# sensor-tiny2313a.net
KiCad netlist of a schematic drawn in EAGLE
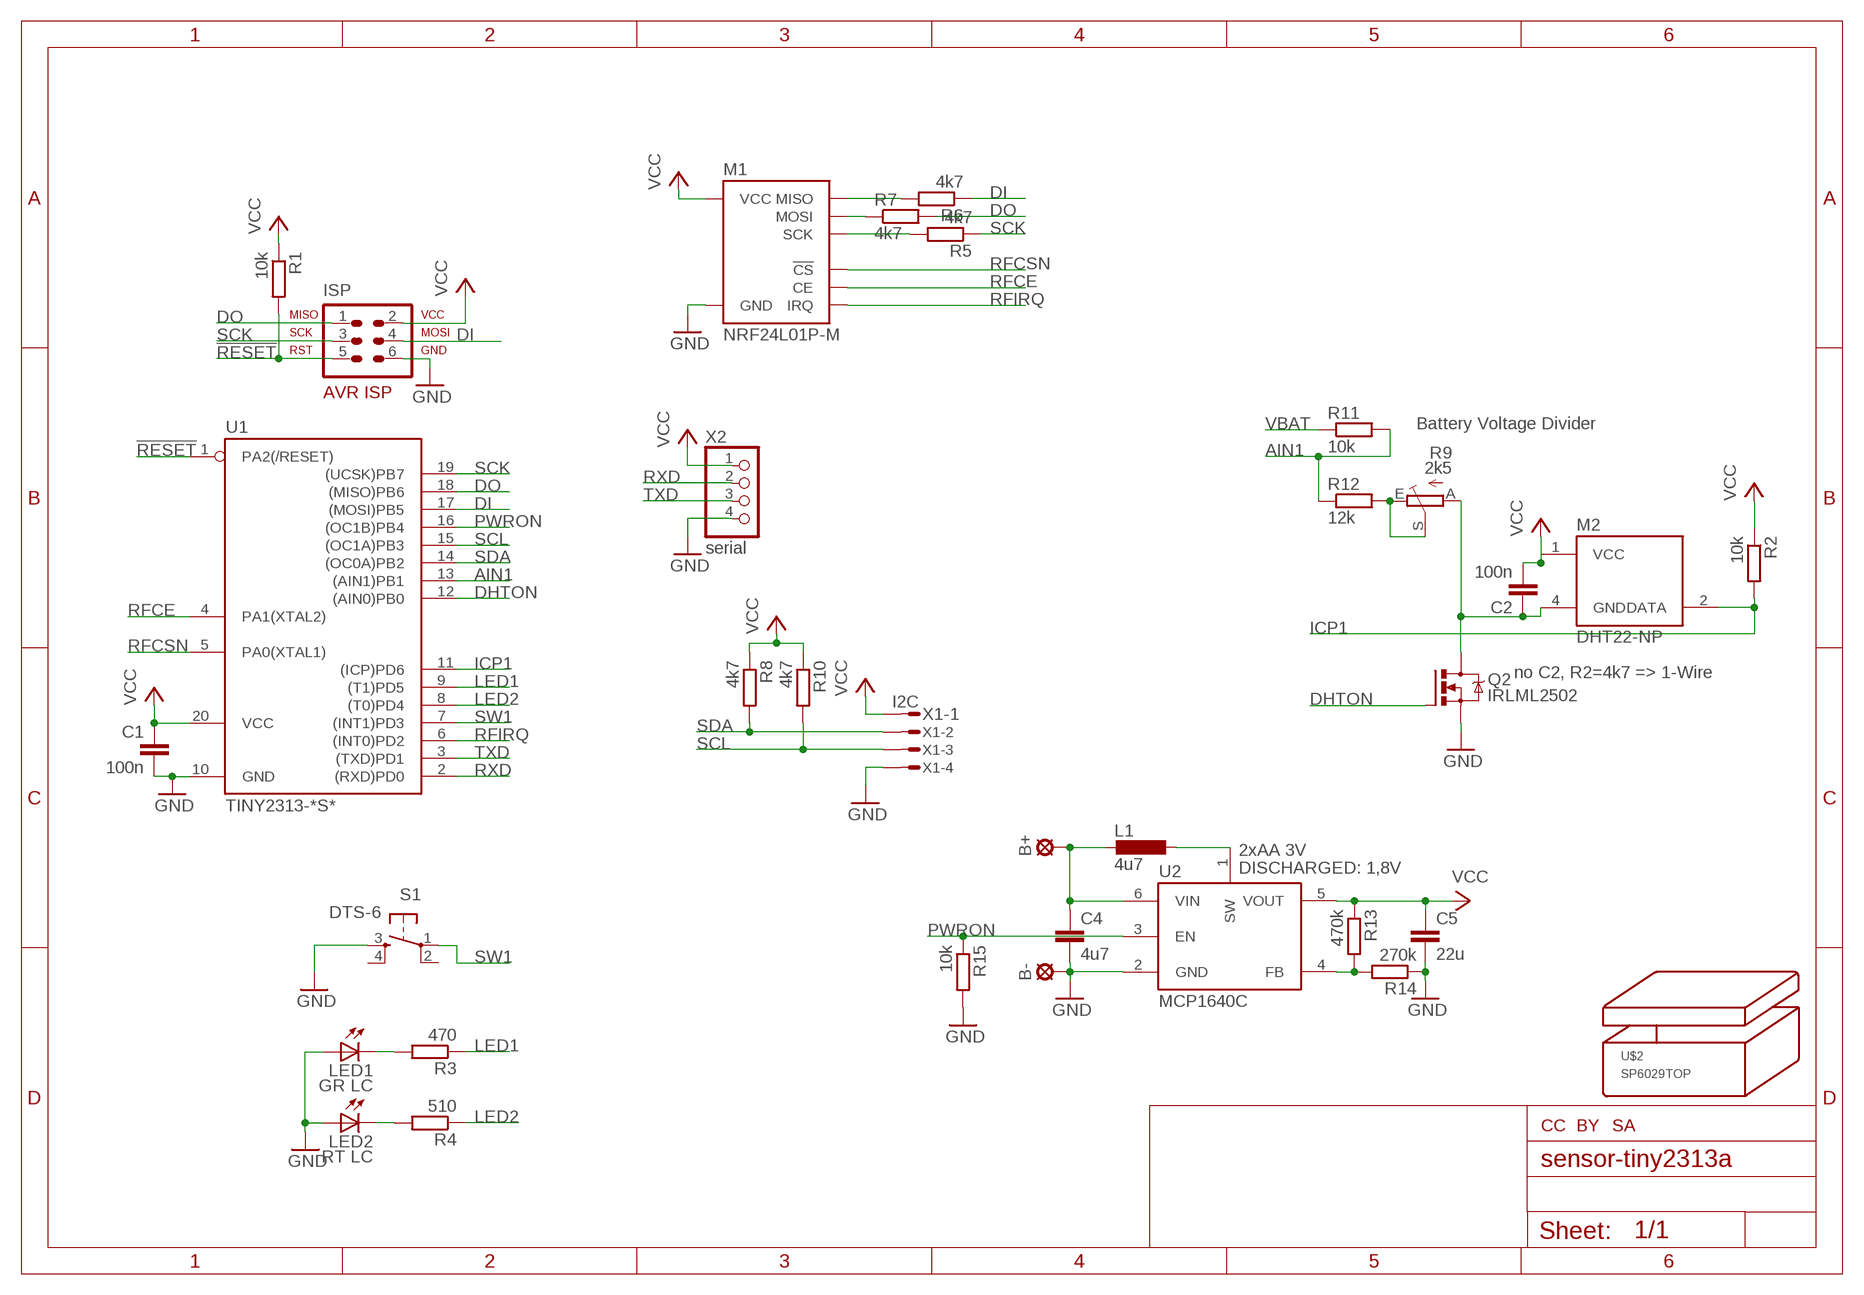
[diagram p0: schematic, sheet 1]

(export (version "E")
  (design (tool "Eeschema 10.0.6"))
  (components
    (comp (ref "B+")
      (value "LSP11")
      (footprint "eagle-import:LSP11")
      (libsource (lib "eagle-import") (part "LSP11"))
    )
    (comp (ref "B-")
      (value "LSP11")
      (footprint "eagle-import:LSP11")
      (libsource (lib "eagle-import") (part "LSP11"))
    )
    (comp (ref "C1")
      (value "100n")
      (footprint "eagle-import:C0603")
      (libsource (lib "eagle-import") (part "C-EUC0603"))
    )
    (comp (ref "C2")
      (value "100n")
      (footprint "eagle-import:C0603")
      (libsource (lib "eagle-import") (part "C-EUC0603"))
    )
    (comp (ref "C4")
      (value "4u7")
      (footprint "eagle-import:C0805")
      (libsource (lib "eagle-import") (part "C-EUC0805"))
    )
    (comp (ref "C5")
      (value "22u")
      (footprint "eagle-import:C1206")
      (libsource (lib "eagle-import") (part "C-EUC1206"))
    )
    (comp (ref "ISP")
      (value "ML6")
      (footprint "eagle-import:AVR-ISP-6")
      (libsource (lib "eagle-import") (part "AVR-ISP-6VERT"))
    )
    (comp (ref "L1")
      (value "4u7")
      (footprint "eagle-import:PISG")
      (libsource (lib "eagle-import") (part "L-EUPISG"))
    )
    (comp (ref "LED1")
      (value "GR LC")
      (footprint "eagle-import:LED5MM")
      (libsource (lib "eagle-import") (part "LED5MM"))
    )
    (comp (ref "LED2")
      (value "RT LC")
      (footprint "eagle-import:LED5MM")
      (libsource (lib "eagle-import") (part "LED5MM"))
    )
    (comp (ref "M1")
      (value "NRF24L01P-M")
      (footprint "eagle-import:NRF24L01P-A")
      (libsource (lib "eagle-import") (part "NRF24L01P-M"))
    )
    (comp (ref "M2")
      (value "DHT22-NP")
      (footprint "eagle-import:DHT22-NOPRINT")
      (libsource (lib "eagle-import") (part "DHT22-NP"))
    )
    (comp (ref "Q2")
      (value "IRLML2502")
      (footprint "eagle-import:MICRO3")
      (libsource (lib "eagle-import") (part "IRLML2502"))
    )
    (comp (ref "R1")
      (value "10k")
      (footprint "eagle-import:R0603")
      (libsource (lib "eagle-import") (part "R-EU_R0603"))
    )
    (comp (ref "R2")
      (value "10k")
      (footprint "eagle-import:R0603")
      (libsource (lib "eagle-import") (part "R-EU_R0603"))
    )
    (comp (ref "R3")
      (value "470")
      (footprint "eagle-import:R0603")
      (libsource (lib "eagle-import") (part "R-EU_R0603"))
    )
    (comp (ref "R4")
      (value "510")
      (footprint "eagle-import:R0603")
      (libsource (lib "eagle-import") (part "R-EU_R0603"))
    )
    (comp (ref "R5")
      (value "4k7")
      (footprint "eagle-import:R0603")
      (libsource (lib "eagle-import") (part "R-EU_R0603"))
    )
    (comp (ref "R6")
      (value "4k7")
      (footprint "eagle-import:R0603")
      (libsource (lib "eagle-import") (part "R-EU_R0603"))
    )
    (comp (ref "R7")
      (value "4k7")
      (footprint "eagle-import:R0603")
      (libsource (lib "eagle-import") (part "R-EU_R0603"))
    )
    (comp (ref "R8")
      (value "4k7")
      (footprint "eagle-import:R0603")
      (libsource (lib "eagle-import") (part "R-EU_R0603"))
    )
    (comp (ref "R9")
      (value "2k5")
      (footprint "eagle-import:CA6H")
      (libsource (lib "eagle-import") (part "TRIM_EU-CA6H"))
    )
    (comp (ref "R10")
      (value "4k7")
      (footprint "eagle-import:R0603")
      (libsource (lib "eagle-import") (part "R-EU_R0603"))
    )
    (comp (ref "R11")
      (value "10k")
      (footprint "eagle-import:R0603")
      (libsource (lib "eagle-import") (part "R-EU_R0603"))
    )
    (comp (ref "R12")
      (value "12k")
      (footprint "eagle-import:R0603")
      (libsource (lib "eagle-import") (part "R-EU_R0603"))
    )
    (comp (ref "R13")
      (value "470k")
      (footprint "eagle-import:R0603")
      (libsource (lib "eagle-import") (part "R-EU_R0603"))
    )
    (comp (ref "R14")
      (value "270k")
      (footprint "eagle-import:R0603")
      (libsource (lib "eagle-import") (part "R-EU_R0603"))
    )
    (comp (ref "R15")
      (value "10k")
      (footprint "eagle-import:R0603")
      (libsource (lib "eagle-import") (part "R-EU_R0603"))
    )
    (comp (ref "S1")
      (value "DTS-6")
      (footprint "eagle-import:DTS-6")
      (libsource (lib "eagle-import") (part "DTS-6"))
    )
    (comp (ref "U$1")
      (value "CC-TPLACE-HALF")
      (footprint "eagle-import:CC_TPLACE_HS")
      (libsource (lib "eagle-import") (part "CC-TPLACE-HALF"))
    )
    (comp (ref "U$2")
      (value "SP6029TOP")
      (footprint "eagle-import:SP6029T")
      (libsource (lib "eagle-import") (part "SP6029TOP"))
    )
    (comp (ref "U$3")
      (value "BY-TPLACE-HS")
      (footprint "eagle-import:BY_TPLACE_HS")
      (libsource (lib "eagle-import") (part "BY-TPLACE-HS"))
    )
    (comp (ref "U$4")
      (value "SA-TPLACE-HALF")
      (footprint "eagle-import:SA_TPLACE_HS")
      (libsource (lib "eagle-import") (part "SA-TPLACE-HALF"))
    )
    (comp (ref "U1")
      (value "TINY2313-*S*")
      (footprint "eagle-import:SO20L$")
      (libsource (lib "eagle-import") (part "TINY2313-S"))
    )
    (comp (ref "U2")
      (value "MCP1640C")
      (footprint "eagle-import:SOT23-6")
      (libsource (lib "eagle-import") (part "MCP1640"))
    )
    (comp (ref "X1")
      (value "I2C")
      (footprint "eagle-import:MICROMATCH-4")
      (libsource (lib "eagle-import") (part "MICROMATCH-4"))
    )
    (comp (ref "X2")
      (value "serial")
      (footprint "eagle-import:1X04")
      (libsource (lib "eagle-import") (part "PINHD-1X4_2.54"))
    )
  )
  (nets
    (net (code "1") (name "/AIN1") (class "Default")
      (node (ref "R11") (pin "2") (pinfunction "2_2") (pintype "passive"))
      (node (ref "R12") (pin "1") (pinfunction "1_1") (pintype "passive"))
      (node (ref "U1") (pin "13") (pinfunction "(AIN1)PB1_13") (pintype "bidirectional"))
    )
    (net (code "2") (name "/DHTON") (class "Default")
      (node (ref "Q2") (pin "1") (pinfunction "G_1") (pintype "passive"))
      (node (ref "U1") (pin "12") (pinfunction "(AIN0)PB0_12") (pintype "bidirectional"))
    )
    (net (code "3") (name "/DI") (class "Default")
      (node (ref "ISP") (pin "4") (pinfunction "4_4") (pintype "passive"))
      (node (ref "R6") (pin "1") (pinfunction "1_1") (pintype "passive"))
      (node (ref "U1") (pin "17") (pinfunction "(MOSI)PB5_17") (pintype "bidirectional"))
    )
    (net (code "4") (name "/DO") (class "Default")
      (node (ref "ISP") (pin "1") (pinfunction "1_1") (pintype "passive"))
      (node (ref "R7") (pin "2") (pinfunction "2_2") (pintype "passive"))
      (node (ref "U1") (pin "18") (pinfunction "(MISO)PB6_18") (pintype "bidirectional"))
    )
    (net (code "5") (name "/ICP1") (class "Default")
      (node (ref "M2") (pin "2") (pinfunction "DATA_2") (pintype "bidirectional"))
      (node (ref "R2") (pin "2") (pinfunction "2_2") (pintype "passive"))
      (node (ref "U1") (pin "11") (pinfunction "(ICP)PD6_11") (pintype "bidirectional"))
    )
    (net (code "6") (name "/LED1") (class "Default")
      (node (ref "R3") (pin "1") (pinfunction "1_1") (pintype "passive"))
      (node (ref "U1") (pin "9") (pinfunction "(T1)PD5_9") (pintype "bidirectional"))
    )
    (net (code "7") (name "/LED2") (class "Default")
      (node (ref "R4") (pin "1") (pinfunction "1_1") (pintype "passive"))
      (node (ref "U1") (pin "8") (pinfunction "(T0)PD4_8") (pintype "bidirectional"))
    )
    (net (code "8") (name "/PWRON") (class "Default")
      (node (ref "R15") (pin "1") (pinfunction "1_1") (pintype "passive"))
      (node (ref "U1") (pin "16") (pinfunction "(OC1B)PB4_16") (pintype "bidirectional"))
      (node (ref "U2") (pin "3") (pinfunction "EN_3") (pintype "input"))
    )
    (net (code "9") (name "/RFCE") (class "Default")
      (node (ref "M1") (pin "CE") (pinfunction "CE_CE") (pintype "input"))
      (node (ref "U1") (pin "4") (pinfunction "PA1(XTAL2)_4") (pintype "bidirectional"))
    )
    (net (code "10") (name "/RFCSN") (class "Default")
      (node (ref "M1") (pin "CSN") (pinfunction "~{CS}_CSN") (pintype "input"))
      (node (ref "U1") (pin "5") (pinfunction "PA0(XTAL1)_5") (pintype "bidirectional"))
    )
    (net (code "11") (name "/RFIRQ") (class "Default")
      (node (ref "M1") (pin "IRQ") (pinfunction "IRQ_IRQ") (pintype "output"))
      (node (ref "U1") (pin "6") (pinfunction "(INT0)PD2_6") (pintype "bidirectional"))
    )
    (net (code "12") (name "/RXD") (class "Default")
      (node (ref "U1") (pin "2") (pinfunction "(RXD)PD0_2") (pintype "bidirectional"))
      (node (ref "X2") (pin "2") (pinfunction "2_2") (pintype "passive"))
    )
    (net (code "13") (name "/SCK") (class "Default")
      (node (ref "ISP") (pin "3") (pinfunction "3_3") (pintype "passive"))
      (node (ref "R5") (pin "1") (pinfunction "1_1") (pintype "passive"))
      (node (ref "U1") (pin "19") (pinfunction "(UCSK)PB7_19") (pintype "bidirectional"))
    )
    (net (code "14") (name "/SCL") (class "Default")
      (node (ref "R10") (pin "2") (pinfunction "2_2") (pintype "passive"))
      (node (ref "U1") (pin "15") (pinfunction "(OC1A)PB3_15") (pintype "bidirectional"))
      (node (ref "X1") (pin "3") (pinfunction "S_3") (pintype "passive"))
    )
    (net (code "15") (name "/SDA") (class "Default")
      (node (ref "R8") (pin "2") (pinfunction "2_2") (pintype "passive"))
      (node (ref "U1") (pin "14") (pinfunction "(OC0A)PB2_14") (pintype "bidirectional"))
      (node (ref "X1") (pin "2") (pinfunction "S_2") (pintype "passive"))
    )
    (net (code "16") (name "/SW1") (class "Default")
      (node (ref "S1") (pin "1") (pinfunction "1_1") (pintype "passive"))
      (node (ref "U1") (pin "7") (pinfunction "(INT1)PD3_7") (pintype "bidirectional"))
    )
    (net (code "17") (name "/TXD") (class "Default")
      (node (ref "U1") (pin "3") (pinfunction "(TXD)PD1_3") (pintype "bidirectional"))
      (node (ref "X2") (pin "3") (pinfunction "3_3") (pintype "passive"))
    )
    (net (code "18") (name "/VBAT") (class "Default")
      (node (ref "B+") (pin "MP") (pinfunction "MP_MP") (pintype "passive"))
      (node (ref "C4") (pin "1") (pinfunction "1_1") (pintype "passive"))
      (node (ref "L1") (pin "2") (pinfunction "2_2") (pintype "passive"))
      (node (ref "R11") (pin "1") (pinfunction "1_1") (pintype "passive"))
      (node (ref "U2") (pin "6") (pinfunction "VIN_6") (pintype "power_in"))
    )
    (net (code "19") (name "/~{RESET}") (class "Default")
      (node (ref "ISP") (pin "5") (pinfunction "5_5") (pintype "passive"))
      (node (ref "R1") (pin "2") (pinfunction "2_2") (pintype "passive"))
      (node (ref "U1") (pin "1") (pinfunction "PA2(/RESET)_1") (pintype "input"))
    )
    (net (code "20") (name "GND") (class "Default")
      (node (ref "B-") (pin "MP") (pinfunction "MP_MP") (pintype "passive"))
      (node (ref "C1") (pin "2") (pinfunction "2_2") (pintype "passive"))
      (node (ref "C4") (pin "2") (pinfunction "2_2") (pintype "passive"))
      (node (ref "C5") (pin "2") (pinfunction "2_2") (pintype "passive"))
      (node (ref "ISP") (pin "6") (pinfunction "6_6") (pintype "passive"))
      (node (ref "LED1") (pin "A") (pinfunction "A_A") (pintype "passive"))
      (node (ref "LED2") (pin "A") (pinfunction "A_A") (pintype "passive"))
      (node (ref "M1") (pin "GND_A") (pinfunction "GND_GND_A") (pintype "power_in"))
      (node (ref "M1") (pin "GND_B") (pinfunction "GND_GND_B") (pintype "power_in"))
      (node (ref "Q2") (pin "2") (pinfunction "S_2") (pintype "passive"))
      (node (ref "R14") (pin "1") (pinfunction "1_1") (pintype "passive"))
      (node (ref "R15") (pin "2") (pinfunction "2_2") (pintype "passive"))
      (node (ref "S1") (pin "3") (pinfunction "3_3") (pintype "passive"))
      (node (ref "U1") (pin "10") (pinfunction "GND_10") (pintype "power_in"))
      (node (ref "U2") (pin "2") (pinfunction "GND_2") (pintype "power_in"))
      (node (ref "X1") (pin "4") (pinfunction "S_4") (pintype "passive"))
      (node (ref "X2") (pin "4") (pinfunction "4_4") (pintype "passive"))
    )
    (net (code "21") (name "Net-(LED1-C)") (class "Default")
      (node (ref "LED1") (pin "K") (pinfunction "C_K") (pintype "passive"))
      (node (ref "R3") (pin "2") (pinfunction "2_2") (pintype "passive"))
    )
    (net (code "22") (name "Net-(LED2-C)") (class "Default")
      (node (ref "LED2") (pin "K") (pinfunction "C_K") (pintype "passive"))
      (node (ref "R4") (pin "2") (pinfunction "2_2") (pintype "passive"))
    )
    (net (code "23") (name "Net-(M1-PadMISO)") (class "Default")
      (node (ref "M1") (pin "MISO") (pinfunction "MISO_MISO") (pintype "output"))
      (node (ref "R6") (pin "2") (pinfunction "2_2") (pintype "passive"))
    )
    (net (code "24") (name "Net-(M1-PadMOSI)") (class "Default")
      (node (ref "M1") (pin "MOSI") (pinfunction "MOSI_MOSI") (pintype "input"))
      (node (ref "R7") (pin "1") (pinfunction "1_1") (pintype "passive"))
    )
    (net (code "25") (name "Net-(M1-PadSCK)") (class "Default")
      (node (ref "M1") (pin "SCK") (pinfunction "SCK_SCK") (pintype "bidirectional"))
      (node (ref "R5") (pin "2") (pinfunction "2_2") (pintype "passive"))
    )
    (net (code "26") (name "Net-(M2-GND)") (class "Default")
      (node (ref "C2") (pin "1") (pinfunction "1_1") (pintype "passive"))
      (node (ref "M2") (pin "4") (pinfunction "GND_4") (pintype "power_in"))
      (node (ref "Q2") (pin "3") (pinfunction "D_3") (pintype "passive"))
      (node (ref "R9") (pin "A") (pinfunction "A_A") (pintype "passive"))
    )
    (net (code "27") (name "Net-(R12-Pad2)") (class "Default")
      (node (ref "R12") (pin "2") (pinfunction "2_2") (pintype "passive"))
      (node (ref "R9") (pin "E") (pinfunction "E_E") (pintype "passive"))
      (node (ref "R9") (pin "S") (pinfunction "S_S") (pintype "passive"))
    )
    (net (code "28") (name "Net-(U2-FB)") (class "Default")
      (node (ref "R13") (pin "2") (pinfunction "2_2") (pintype "passive"))
      (node (ref "R14") (pin "2") (pinfunction "2_2") (pintype "passive"))
      (node (ref "U2") (pin "4") (pinfunction "FB_4") (pintype "input"))
    )
    (net (code "29") (name "Net-(U2-SW)") (class "Default")
      (node (ref "L1") (pin "1") (pinfunction "1_1") (pintype "passive"))
      (node (ref "U2") (pin "1") (pinfunction "SW_1") (pintype "passive"))
    )
    (net (code "30") (name "VCC") (class "Default")
      (node (ref "C1") (pin "1") (pinfunction "1_1") (pintype "passive"))
      (node (ref "C2") (pin "2") (pinfunction "2_2") (pintype "passive"))
      (node (ref "C5") (pin "1") (pinfunction "1_1") (pintype "passive"))
      (node (ref "ISP") (pin "2") (pinfunction "2_2") (pintype "passive"))
      (node (ref "M1") (pin "VCC_A") (pinfunction "VCC_VCC_A") (pintype "power_in"))
      (node (ref "M1") (pin "VCC_B") (pinfunction "VCC_VCC_B") (pintype "power_in"))
      (node (ref "M2") (pin "1") (pinfunction "VCC_1") (pintype "power_in"))
      (node (ref "R1") (pin "1") (pinfunction "1_1") (pintype "passive"))
      (node (ref "R10") (pin "1") (pinfunction "1_1") (pintype "passive"))
      (node (ref "R13") (pin "1") (pinfunction "1_1") (pintype "passive"))
      (node (ref "R2") (pin "1") (pinfunction "1_1") (pintype "passive"))
      (node (ref "R8") (pin "1") (pinfunction "1_1") (pintype "passive"))
      (node (ref "U1") (pin "20") (pinfunction "VCC_20") (pintype "power_in"))
      (node (ref "U2") (pin "5") (pinfunction "VOUT_5") (pintype "power_in"))
      (node (ref "X1") (pin "1") (pinfunction "S_1") (pintype "passive"))
      (node (ref "X2") (pin "1") (pinfunction "1_1") (pintype "passive"))
    )
    (net (code "31") (name "unconnected-(S1-Pad2)") (class "Default")
      (node (ref "S1") (pin "2") (pinfunction "2_2") (pintype "passive"))
    )
    (net (code "32") (name "unconnected-(S1-Pad4)") (class "Default")
      (node (ref "S1") (pin "4") (pinfunction "4_4") (pintype "passive"))
    )
  )
)
